# RcMPPT-BMS-BFE.net
KiCad netlist of a schematic drawn in Altium Designer
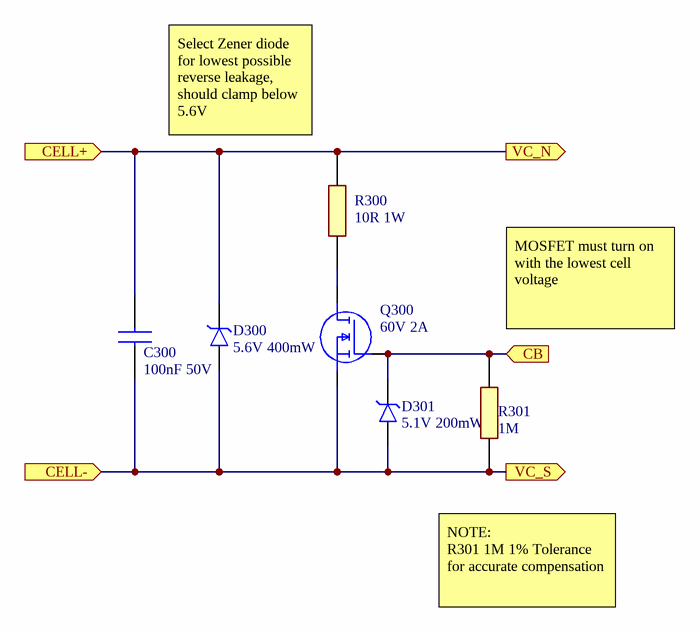
[diagram p0: RcMPPT-BMS-BFE.SchDoc]

(export (version "E")
  (design (tool "Eeschema 10.0.6"))
  (components
    (comp (ref "C300")
      (value "100nF 50V")
      (footprint "CAPC1608X97N")
      (description "Capacitor")
      (libsource (lib "RcMPPTLib") (part "C0603"))
    )
    (comp (ref "D300")
      (value "5.6V 400mW")
      (footprint "SOD-123FL")
      (description "ZENER Diode")
      (libsource (lib "RcMPPTLib") (part "ZENER-DIODE"))
    )
    (comp (ref "D301")
      (value "5.1V 200mW")
      (footprint "SOD-323")
      (description "ZENER Diode")
      (libsource (lib "RcMPPTLib") (part "ZENER-DIODE"))
    )
    (comp (ref "Q300")
      (value "60V 2A")
      (footprint "SOT96P240X110-3N")
      (description "MOSFET (N-Channel)")
      (libsource (lib "RcMPPTLib") (part "NMOS"))
    )
    (comp (ref "R300")
      (value "10R 1W")
      (footprint "RESC6331X75N")
      (description "Resistor")
      (libsource (lib "RcMPPTLib") (part "R2512"))
    )
    (comp (ref "R301")
      (value "1M")
      (footprint "RESC1005X40N")
      (description "Resistor")
      (libsource (lib "RcMPPTLib") (part "R0402"))
    )
  )
  (nets
    (net (code "1") (name "/CB") (class "Default")
      (node (ref "D301") (pin "1") (pinfunction "K_1") (pintype "passive"))
      (node (ref "Q300") (pin "1") (pinfunction "G_1") (pintype "passive"))
      (node (ref "R301") (pin "2") (pinfunction "2_2") (pintype "passive"))
    )
    (net (code "2") (name "/CELL+") (class "Default")
      (node (ref "C300") (pin "2") (pinfunction "2_2") (pintype "passive"))
      (node (ref "D300") (pin "1") (pinfunction "K_1") (pintype "passive"))
      (node (ref "R300") (pin "2") (pinfunction "2_2") (pintype "passive"))
    )
    (net (code "3") (name "/CELL-") (class "Default")
      (node (ref "C300") (pin "1") (pinfunction "1_1") (pintype "passive"))
      (node (ref "D300") (pin "2") (pinfunction "A_2") (pintype "passive"))
      (node (ref "D301") (pin "2") (pinfunction "A_2") (pintype "passive"))
      (node (ref "Q300") (pin "2") (pinfunction "S_2") (pintype "passive"))
      (node (ref "R301") (pin "1") (pinfunction "1_1") (pintype "passive"))
    )
    (net (code "4") (name "Net-(Q300-D)") (class "Default")
      (node (ref "Q300") (pin "3") (pinfunction "D_3") (pintype "passive"))
      (node (ref "R300") (pin "1") (pinfunction "1_1") (pintype "passive"))
    )
  )
)
